# MCU.net
KiCad netlist of a schematic drawn in Altium Designer
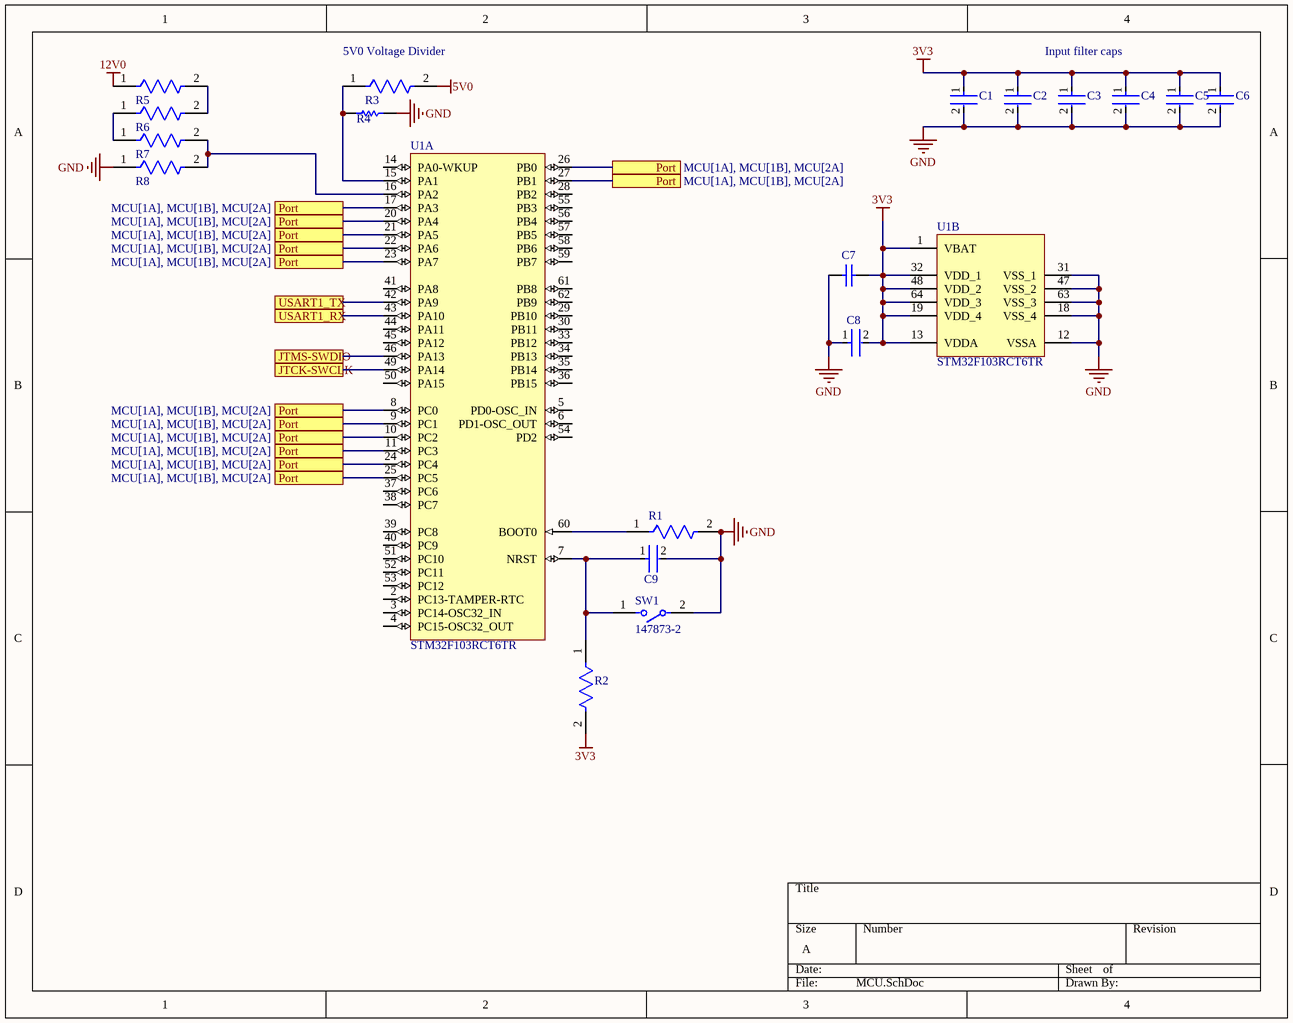
[diagram p0: MCU.SchDoc]

(export (version "E")
  (design (tool "Eeschema 10.0.6"))
  (components
    (comp (ref "C1")
      (value "CL05A104KA5NNNC")
      (footprint "FP-CL278-IPC_C")
      (description "Cap Ceramic 100nF 25V X5R ±10% SMD 0402 +85°C Paper T/R")
      (fields (field (name "VOLTAGE") "25V") (field (name "TOLERANCE") "10%"))
      (libsource (lib "Altium Content Vault") (part "b4654b650e69147ec39a6b967a45e02"))
    )
    (comp (ref "C2")
      (value "CL05A104KA5NNNC")
      (footprint "FP-CL278-IPC_C")
      (description "Cap Ceramic 100nF 25V X5R ±10% SMD 0402 +85°C Paper T/R")
      (fields (field (name "VOLTAGE") "25V") (field (name "TOLERANCE") "10%"))
      (libsource (lib "Altium Content Vault") (part "b4654b650e69147ec39a6b967a45e02"))
    )
    (comp (ref "C3")
      (value "CL05A104KA5NNNC")
      (footprint "FP-CL278-IPC_C")
      (description "Cap Ceramic 100nF 25V X5R ±10% SMD 0402 +85°C Paper T/R")
      (fields (field (name "VOLTAGE") "25V") (field (name "TOLERANCE") "10%"))
      (libsource (lib "Altium Content Vault") (part "b4654b650e69147ec39a6b967a45e02"))
    )
    (comp (ref "C4")
      (value "CL05A104KA5NNNC")
      (footprint "FP-CL278-IPC_C")
      (description "Cap Ceramic 100nF 25V X5R ±10% SMD 0402 +85°C Paper T/R")
      (fields (field (name "VOLTAGE") "25V") (field (name "TOLERANCE") "10%"))
      (libsource (lib "Altium Content Vault") (part "b4654b650e69147ec39a6b967a45e02"))
    )
    (comp (ref "C5")
      (value "CL05A104KA5NNNC")
      (footprint "FP-CL278-IPC_C")
      (description "Cap Ceramic 100nF 25V X5R ±10% SMD 0402 +85°C Paper T/R")
      (fields (field (name "VOLTAGE") "25V") (field (name "TOLERANCE") "10%"))
      (libsource (lib "Altium Content Vault") (part "b4654b650e69147ec39a6b967a45e02"))
    )
    (comp (ref "C6")
      (value "CL05A104KA5NNNC")
      (footprint "FP-CL278-IPC_C")
      (description "Cap Ceramic 100nF 25V X5R ±10% SMD 0402 +85°C Paper T/R")
      (fields (field (name "VOLTAGE") "25V") (field (name "TOLERANCE") "10%"))
      (libsource (lib "Altium Content Vault") (part "b4654b650e69147ec39a6b967a45e02"))
    )
    (comp (ref "C7")
      (value "CL10A475KQ8NNNC")
      (footprint "CAPC1608X90X30LL10T20")
      (description "Chip Capacitor, 4.7 uF, +/- 10%, 6.3 V, -55 to 85 degC, 0603 (1608 Metric), RoHS, Tape and Reel")
      (fields (field (name "MANUFACTURER") "Samsung Electro-Mechanics"))
      (libsource (lib "Altium Content Vault") (part "CAP-NP-2"))
    )
    (comp (ref "C8")
      (value "CL10A105KA8NNNC")
      (footprint "FP-CL10-IPC_C")
      (description "Cap Ceramic 1uF 25V X5R ±10% Pad SMD 0603 +85°C T/R")
      (fields (field (name "VOLTAGE") "25V") (field (name "TOLERANCE") "10%"))
      (libsource (lib "Altium Content Vault") (part "b4654b650e69147ec39a6b967a45e02"))
    )
    (comp (ref "C9")
      (value "CL05A104KA5NNNC")
      (footprint "FP-CL278-IPC_C")
      (description "Cap Ceramic 100nF 25V X5R ±10% SMD 0402 +85°C Paper T/R")
      (fields (field (name "VOLTAGE") "25V") (field (name "TOLERANCE") "10%"))
      (libsource (lib "Altium Content Vault") (part "b4654b650e69147ec39a6b967a45e02"))
    )
    (comp (ref "R1")
      (value "RC0603FR-07100KL")
      (footprint "FP-RC0603-0_55-MFG")
      (description "RES SMD 100K OHM 1% 1/10W 0603")
      (fields (field (name "TOLERANCE") "1%"))
      (libsource (lib "Altium Content Vault") (part "1029c3af85768c4190bb7ad29bc67b5"))
    )
    (comp (ref "R2")
      (value "RC0603FR-07100KL")
      (footprint "FP-RC0603-0_55-MFG")
      (description "RES SMD 100K OHM 1% 1/10W 0603")
      (fields (field (name "TOLERANCE") "1%"))
      (libsource (lib "Altium Content Vault") (part "1029c3af85768c4190bb7ad29bc67b5"))
    )
    (comp (ref "R3")
      (value "RC0603FR-07100KL")
      (footprint "FP-RC0603-0_55-MFG")
      (description "RES SMD 100K OHM 1% 1/10W 0603")
      (fields (field (name "TOLERANCE") "1%"))
      (libsource (lib "Altium Content Vault") (part "1029c3af85768c4190bb7ad29bc67b5"))
    )
    (comp (ref "R4")
      (value "RN73H1ETTP1503B25")
      (footprint "RESC1005X40X25NL10T10")
      (fields (field (name "MANUFACTURER") "KOA Speer"))
      (libsource (lib "Altium Content Vault") (part "RES"))
    )
    (comp (ref "R5")
      (value "RC0603FR-07100KL")
      (footprint "FP-RC0603-0_55-MFG")
      (description "RES SMD 100K OHM 1% 1/10W 0603")
      (fields (field (name "TOLERANCE") "1%"))
      (libsource (lib "Altium Content Vault") (part "1029c3af85768c4190bb7ad29bc67b5"))
    )
    (comp (ref "R6")
      (value "RC0603FR-07100KL")
      (footprint "FP-RC0603-0_55-MFG")
      (description "RES SMD 100K OHM 1% 1/10W 0603")
      (fields (field (name "TOLERANCE") "1%"))
      (libsource (lib "Altium Content Vault") (part "1029c3af85768c4190bb7ad29bc67b5"))
    )
    (comp (ref "R7")
      (value "RC0603FR-07100KL")
      (footprint "FP-RC0603-0_55-MFG")
      (description "RES SMD 100K OHM 1% 1/10W 0603")
      (fields (field (name "TOLERANCE") "1%"))
      (libsource (lib "Altium Content Vault") (part "1029c3af85768c4190bb7ad29bc67b5"))
    )
    (comp (ref "R8")
      (value "RC0603FR-07100KL")
      (footprint "FP-RC0603-0_55-MFG")
      (description "RES SMD 100K OHM 1% 1/10W 0603")
      (fields (field (name "TOLERANCE") "1%"))
      (libsource (lib "Altium Content Vault") (part "1029c3af85768c4190bb7ad29bc67b5"))
    )
    (comp (ref "SW1")
      (value "147873-2")
      (footprint "FP-147873-2-MFG")
      (description "SWITCH TACTILE SPST-NO 0.05A 24V")
      (libsource (lib "Altium Content Vault") (part "dafb00e05129bbbb566f246498240cb"))
    )
    (comp (ref "U1")
      (value "STM32F103RCT6TR")
      (footprint "STM-LQFP64_N")
      (libsource (lib "Altium Content Vault") (part "MC-ARM-STM32F103XC_D_E-SQ64"))
    )
  )
  (nets
    (net (code "1") (name "/JTCK-SWCLK") (class "Default")
      (node (ref "U1") (pin "49") (pinfunction "PA14_49") (pintype "bidirectional"))
    )
    (net (code "2") (name "/JTMS-SWDIO") (class "Default")
      (node (ref "U1") (pin "46") (pinfunction "PA13_46") (pintype "bidirectional"))
    )
    (net (code "3") (name "/Port") (class "Default")
      (node (ref "U1") (pin "10") (pinfunction "PC2_10") (pintype "bidirectional"))
      (node (ref "U1") (pin "11") (pinfunction "PC3_11") (pintype "bidirectional"))
      (node (ref "U1") (pin "17") (pinfunction "PA3_17") (pintype "bidirectional"))
      (node (ref "U1") (pin "20") (pinfunction "PA4_20") (pintype "bidirectional"))
      (node (ref "U1") (pin "21") (pinfunction "PA5_21") (pintype "bidirectional"))
      (node (ref "U1") (pin "22") (pinfunction "PA6_22") (pintype "bidirectional"))
      (node (ref "U1") (pin "23") (pinfunction "PA7_23") (pintype "bidirectional"))
      (node (ref "U1") (pin "24") (pinfunction "PC4_24") (pintype "bidirectional"))
      (node (ref "U1") (pin "25") (pinfunction "PC5_25") (pintype "bidirectional"))
      (node (ref "U1") (pin "26") (pinfunction "PB0_26") (pintype "bidirectional"))
      (node (ref "U1") (pin "27") (pinfunction "PB1_27") (pintype "bidirectional"))
      (node (ref "U1") (pin "8") (pinfunction "PC0_8") (pintype "bidirectional"))
      (node (ref "U1") (pin "9") (pinfunction "PC1_9") (pintype "bidirectional"))
    )
    (net (code "4") (name "/USART1_RX") (class "Default")
      (node (ref "U1") (pin "43") (pinfunction "PA10_43") (pintype "bidirectional"))
    )
    (net (code "5") (name "/USART1_TX") (class "Default")
      (node (ref "U1") (pin "42") (pinfunction "PA9_42") (pintype "bidirectional"))
    )
    (net (code "6") (name "3V3") (class "Default")
      (node (ref "C1") (pin "1") (pinfunction "1_1") (pintype "passive"))
      (node (ref "C2") (pin "1") (pinfunction "1_1") (pintype "passive"))
      (node (ref "C3") (pin "1") (pinfunction "1_1") (pintype "passive"))
      (node (ref "C4") (pin "1") (pinfunction "1_1") (pintype "passive"))
      (node (ref "C5") (pin "1") (pinfunction "1_1") (pintype "passive"))
      (node (ref "C6") (pin "1") (pinfunction "1_1") (pintype "passive"))
      (node (ref "C7") (pin "1") (pinfunction "1_1") (pintype "passive"))
      (node (ref "C8") (pin "2") (pinfunction "2_2") (pintype "passive"))
      (node (ref "R2") (pin "2") (pinfunction "2_2") (pintype "passive"))
      (node (ref "U1") (pin "1") (pinfunction "VBAT_1") (pintype "power_in"))
      (node (ref "U1") (pin "13") (pinfunction "VDDA_13") (pintype "power_in"))
      (node (ref "U1") (pin "19") (pinfunction "VDD_4_19") (pintype "power_in"))
      (node (ref "U1") (pin "32") (pinfunction "VDD_1_32") (pintype "power_in"))
      (node (ref "U1") (pin "48") (pinfunction "VDD_2_48") (pintype "power_in"))
      (node (ref "U1") (pin "64") (pinfunction "VDD_3_64") (pintype "power_in"))
    )
    (net (code "7") (name "5V0") (class "Default")
      (node (ref "R3") (pin "2") (pinfunction "2_2") (pintype "passive"))
    )
    (net (code "8") (name "12V0") (class "Default")
      (node (ref "R5") (pin "1") (pinfunction "1_1") (pintype "passive"))
    )
    (net (code "9") (name "GND") (class "Default")
      (node (ref "C1") (pin "2") (pinfunction "2_2") (pintype "passive"))
      (node (ref "C2") (pin "2") (pinfunction "2_2") (pintype "passive"))
      (node (ref "C3") (pin "2") (pinfunction "2_2") (pintype "passive"))
      (node (ref "C4") (pin "2") (pinfunction "2_2") (pintype "passive"))
      (node (ref "C5") (pin "2") (pinfunction "2_2") (pintype "passive"))
      (node (ref "C6") (pin "2") (pinfunction "2_2") (pintype "passive"))
      (node (ref "C7") (pin "2") (pinfunction "2_2") (pintype "passive"))
      (node (ref "C8") (pin "1") (pinfunction "1_1") (pintype "passive"))
      (node (ref "C9") (pin "2") (pinfunction "2_2") (pintype "passive"))
      (node (ref "R1") (pin "2") (pinfunction "2_2") (pintype "passive"))
      (node (ref "R4") (pin "2") (pinfunction "2_2") (pintype "passive"))
      (node (ref "R8") (pin "1") (pinfunction "1_1") (pintype "passive"))
      (node (ref "SW1") (pin "2") (pinfunction "2_2") (pintype "passive"))
      (node (ref "U1") (pin "12") (pinfunction "VSSA_12") (pintype "power_in"))
      (node (ref "U1") (pin "18") (pinfunction "VSS_4_18") (pintype "power_in"))
      (node (ref "U1") (pin "31") (pinfunction "VSS_1_31") (pintype "power_in"))
      (node (ref "U1") (pin "47") (pinfunction "VSS_2_47") (pintype "power_in"))
      (node (ref "U1") (pin "63") (pinfunction "VSS_3_63") (pintype "power_in"))
    )
    (net (code "10") (name "Net-(R5-Pad2)") (class "Default")
      (node (ref "R5") (pin "2") (pinfunction "2_2") (pintype "passive"))
      (node (ref "R6") (pin "2") (pinfunction "2_2") (pintype "passive"))
    )
    (net (code "11") (name "Net-(R6-Pad1)") (class "Default")
      (node (ref "R6") (pin "1") (pinfunction "1_1") (pintype "passive"))
      (node (ref "R7") (pin "1") (pinfunction "1_1") (pintype "passive"))
    )
    (net (code "12") (name "Net-(U1A-BOOT0)") (class "Default")
      (node (ref "R1") (pin "1") (pinfunction "1_1") (pintype "passive"))
      (node (ref "U1") (pin "60") (pinfunction "BOOT0_60") (pintype "input"))
    )
    (net (code "13") (name "Net-(U1A-NRST)") (class "Default")
      (node (ref "C9") (pin "1") (pinfunction "1_1") (pintype "passive"))
      (node (ref "R2") (pin "1") (pinfunction "1_1") (pintype "passive"))
      (node (ref "SW1") (pin "1") (pinfunction "1_1") (pintype "passive"))
      (node (ref "U1") (pin "7") (pinfunction "NRST_7") (pintype "bidirectional"))
    )
    (net (code "14") (name "Net-(U1A-PA1)") (class "Default")
      (node (ref "R3") (pin "1") (pinfunction "1_1") (pintype "passive"))
      (node (ref "R4") (pin "1") (pinfunction "1_1") (pintype "passive"))
      (node (ref "U1") (pin "15") (pinfunction "PA1_15") (pintype "bidirectional"))
    )
    (net (code "15") (name "Net-(U1A-PA2)") (class "Default")
      (node (ref "R7") (pin "2") (pinfunction "2_2") (pintype "passive"))
      (node (ref "R8") (pin "2") (pinfunction "2_2") (pintype "passive"))
      (node (ref "U1") (pin "16") (pinfunction "PA2_16") (pintype "bidirectional"))
    )
    (net (code "16") (name "unconnected-(U1A-PA0-WKUP-Pad14)") (class "Default")
      (node (ref "U1") (pin "14") (pinfunction "PA0-WKUP_14") (pintype "bidirectional"))
    )
    (net (code "17") (name "unconnected-(U1A-PA8-Pad41)") (class "Default")
      (node (ref "U1") (pin "41") (pinfunction "PA8_41") (pintype "bidirectional"))
    )
    (net (code "18") (name "unconnected-(U1A-PA11-Pad44)") (class "Default")
      (node (ref "U1") (pin "44") (pinfunction "PA11_44") (pintype "bidirectional"))
    )
    (net (code "19") (name "unconnected-(U1A-PA12-Pad45)") (class "Default")
      (node (ref "U1") (pin "45") (pinfunction "PA12_45") (pintype "bidirectional"))
    )
    (net (code "20") (name "unconnected-(U1A-PA15-Pad50)") (class "Default")
      (node (ref "U1") (pin "50") (pinfunction "PA15_50") (pintype "bidirectional"))
    )
    (net (code "21") (name "unconnected-(U1A-PB2-Pad28)") (class "Default")
      (node (ref "U1") (pin "28") (pinfunction "PB2_28") (pintype "bidirectional"))
    )
    (net (code "22") (name "unconnected-(U1A-PB3-Pad55)") (class "Default")
      (node (ref "U1") (pin "55") (pinfunction "PB3_55") (pintype "bidirectional"))
    )
    (net (code "23") (name "unconnected-(U1A-PB4-Pad56)") (class "Default")
      (node (ref "U1") (pin "56") (pinfunction "PB4_56") (pintype "bidirectional"))
    )
    (net (code "24") (name "unconnected-(U1A-PB5-Pad57)") (class "Default")
      (node (ref "U1") (pin "57") (pinfunction "PB5_57") (pintype "bidirectional"))
    )
    (net (code "25") (name "unconnected-(U1A-PB6-Pad58)") (class "Default")
      (node (ref "U1") (pin "58") (pinfunction "PB6_58") (pintype "bidirectional"))
    )
    (net (code "26") (name "unconnected-(U1A-PB7-Pad59)") (class "Default")
      (node (ref "U1") (pin "59") (pinfunction "PB7_59") (pintype "bidirectional"))
    )
    (net (code "27") (name "unconnected-(U1A-PB8-Pad61)") (class "Default")
      (node (ref "U1") (pin "61") (pinfunction "PB8_61") (pintype "bidirectional"))
    )
    (net (code "28") (name "unconnected-(U1A-PB9-Pad62)") (class "Default")
      (node (ref "U1") (pin "62") (pinfunction "PB9_62") (pintype "bidirectional"))
    )
    (net (code "29") (name "unconnected-(U1A-PB10-Pad29)") (class "Default")
      (node (ref "U1") (pin "29") (pinfunction "PB10_29") (pintype "bidirectional"))
    )
    (net (code "30") (name "unconnected-(U1A-PB11-Pad30)") (class "Default")
      (node (ref "U1") (pin "30") (pinfunction "PB11_30") (pintype "bidirectional"))
    )
    (net (code "31") (name "unconnected-(U1A-PB12-Pad33)") (class "Default")
      (node (ref "U1") (pin "33") (pinfunction "PB12_33") (pintype "bidirectional"))
    )
    (net (code "32") (name "unconnected-(U1A-PB13-Pad34)") (class "Default")
      (node (ref "U1") (pin "34") (pinfunction "PB13_34") (pintype "bidirectional"))
    )
    (net (code "33") (name "unconnected-(U1A-PB14-Pad35)") (class "Default")
      (node (ref "U1") (pin "35") (pinfunction "PB14_35") (pintype "bidirectional"))
    )
    (net (code "34") (name "unconnected-(U1A-PB15-Pad36)") (class "Default")
      (node (ref "U1") (pin "36") (pinfunction "PB15_36") (pintype "bidirectional"))
    )
    (net (code "35") (name "unconnected-(U1A-PC6-Pad37)") (class "Default")
      (node (ref "U1") (pin "37") (pinfunction "PC6_37") (pintype "bidirectional"))
    )
    (net (code "36") (name "unconnected-(U1A-PC7-Pad38)") (class "Default")
      (node (ref "U1") (pin "38") (pinfunction "PC7_38") (pintype "bidirectional"))
    )
    (net (code "37") (name "unconnected-(U1A-PC8-Pad39)") (class "Default")
      (node (ref "U1") (pin "39") (pinfunction "PC8_39") (pintype "bidirectional"))
    )
    (net (code "38") (name "unconnected-(U1A-PC9-Pad40)") (class "Default")
      (node (ref "U1") (pin "40") (pinfunction "PC9_40") (pintype "bidirectional"))
    )
    (net (code "39") (name "unconnected-(U1A-PC10-Pad51)") (class "Default")
      (node (ref "U1") (pin "51") (pinfunction "PC10_51") (pintype "bidirectional"))
    )
    (net (code "40") (name "unconnected-(U1A-PC11-Pad52)") (class "Default")
      (node (ref "U1") (pin "52") (pinfunction "PC11_52") (pintype "bidirectional"))
    )
    (net (code "41") (name "unconnected-(U1A-PC12-Pad53)") (class "Default")
      (node (ref "U1") (pin "53") (pinfunction "PC12_53") (pintype "bidirectional"))
    )
    (net (code "42") (name "unconnected-(U1A-PC13-TAMPER-RTC-Pad2)") (class "Default")
      (node (ref "U1") (pin "2") (pinfunction "PC13-TAMPER-RTC_2") (pintype "bidirectional"))
    )
    (net (code "43") (name "unconnected-(U1A-PC14-OSC32_IN-Pad3)") (class "Default")
      (node (ref "U1") (pin "3") (pinfunction "PC14-OSC32_IN_3") (pintype "bidirectional"))
    )
    (net (code "44") (name "unconnected-(U1A-PC15-OSC32_OUT-Pad4)") (class "Default")
      (node (ref "U1") (pin "4") (pinfunction "PC15-OSC32_OUT_4") (pintype "bidirectional"))
    )
    (net (code "45") (name "unconnected-(U1A-PD0-OSC_IN-Pad5)") (class "Default")
      (node (ref "U1") (pin "5") (pinfunction "PD0-OSC_IN_5") (pintype "bidirectional"))
    )
    (net (code "46") (name "unconnected-(U1A-PD1-OSC_OUT-Pad6)") (class "Default")
      (node (ref "U1") (pin "6") (pinfunction "PD1-OSC_OUT_6") (pintype "bidirectional"))
    )
    (net (code "47") (name "unconnected-(U1A-PD2-Pad54)") (class "Default")
      (node (ref "U1") (pin "54") (pinfunction "PD2_54") (pintype "bidirectional"))
    )
  )
)
